# HC-SR04_v4_SCH.net
KiCad netlist of a schematic drawn in Altium Designer
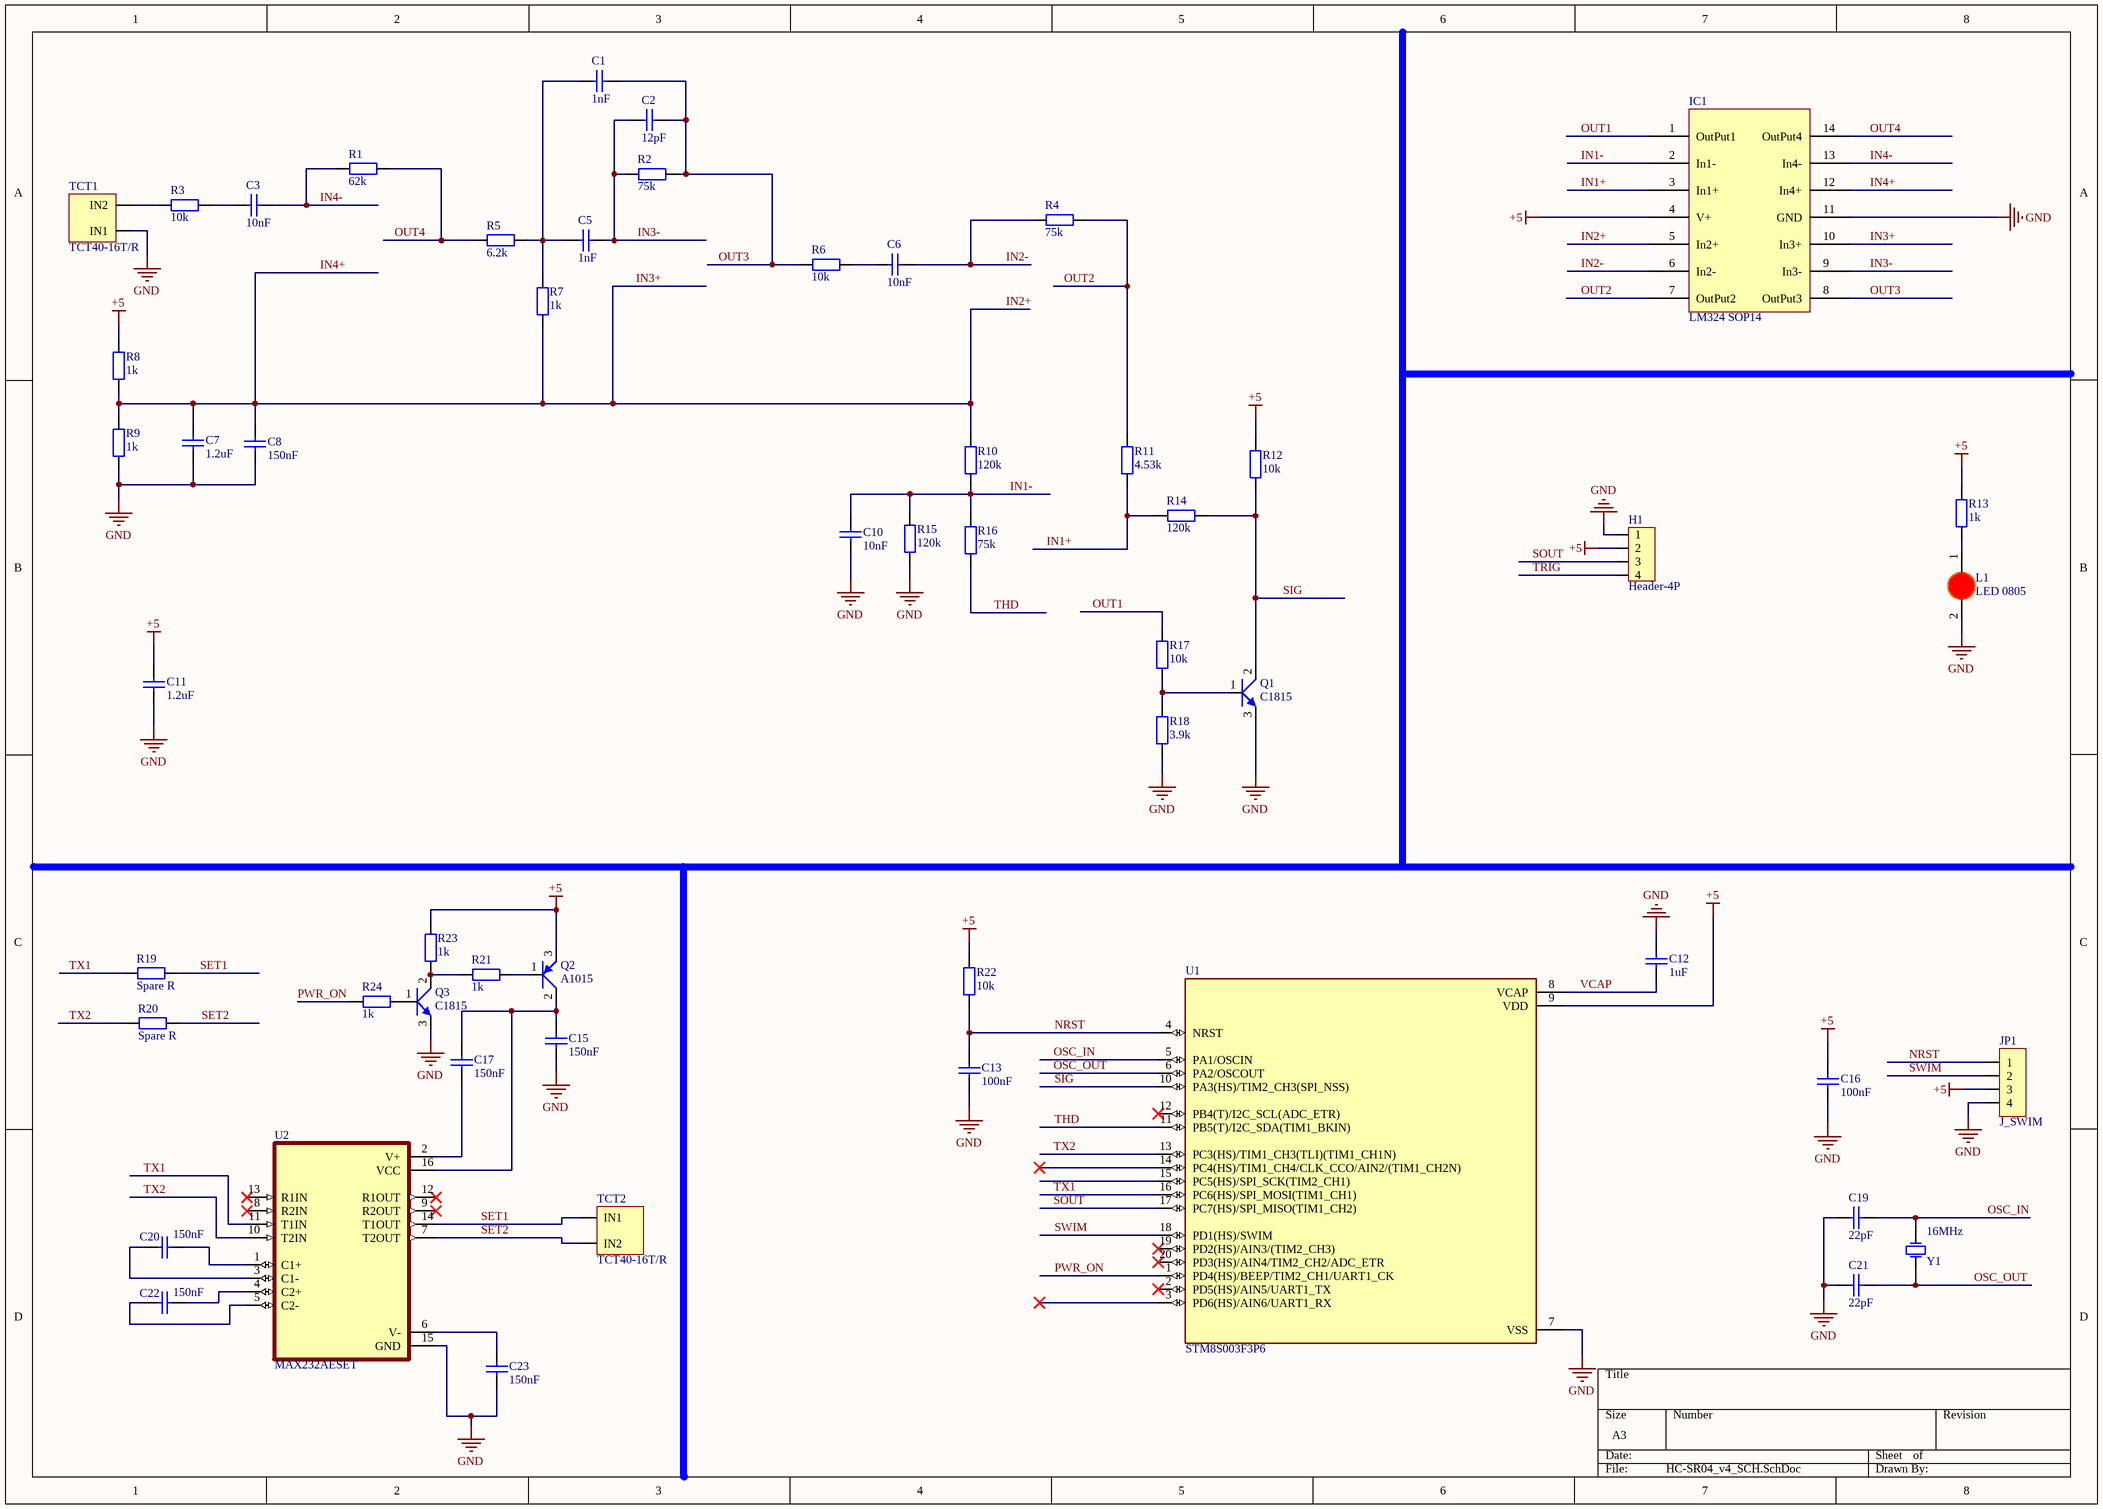
[diagram p0: HC-SR04_v4_SCH.SchDoc]

(export (version "E")
  (design (tool "Eeschema 10.0.6"))
  (components
    (comp (ref "C1")
      (value "1nF")
      (footprint "XLib:CAP_SMD_0603")
      (description "Dán")
      (libsource (lib "namnt_Lib") (part "Tu 0603 102 50V 10%"))
    )
    (comp (ref "C2")
      (value "12pF")
      (footprint "XLib:CAP_SMD_0603")
      (description "Dán")
      (libsource (lib "namnt_Lib") (part "Tu 0603 102 50V 10%"))
    )
    (comp (ref "C3")
      (value "10nF")
      (footprint "XLib:CAP_SMD_0603")
      (description "Dán")
      (libsource (lib "namnt_Lib") (part "Tu 0603 103 50V 10%"))
    )
    (comp (ref "C5")
      (value "1nF")
      (footprint "XLib:CAP_SMD_0603")
      (description "Dán")
      (libsource (lib "namnt_Lib") (part "Tu 0603 102 50V 10%"))
    )
    (comp (ref "C6")
      (value "10nF")
      (footprint "XLib:CAP_SMD_0603")
      (description "Dán")
      (libsource (lib "namnt_Lib") (part "Tu 0603 102 50V 10%"))
    )
    (comp (ref "C7")
      (value "1.2uF")
      (footprint "XLib:CAP_SMD_0603")
      (description "Dán")
      (libsource (lib "namnt_Lib") (part "Tu 0603 104 50V 10%"))
    )
    (comp (ref "C8")
      (value "150nF")
      (footprint "XLib:CAP_SMD_0603")
      (description "Dán")
      (libsource (lib "namnt_Lib") (part "Tu 0603 104 50V 10%"))
    )
    (comp (ref "C10")
      (value "10nF")
      (footprint "XLib:CAP_SMD_0603")
      (description "Dán")
      (libsource (lib "namnt_Lib") (part "Tu 0603 102 50V 10%"))
    )
    (comp (ref "C11")
      (value "1.2uF")
      (footprint "XLib:CAP_SMD_0603")
      (description "Dán")
      (libsource (lib "namnt_Lib") (part "Tu 0603 102 50V 10%"))
    )
    (comp (ref "C12")
      (value "1uF")
      (footprint "XLib:CAP_SMD_0603")
      (description "Dán")
      (libsource (lib "namnt_Lib") (part "Tu 0603 102 50V 10%"))
    )
    (comp (ref "C13")
      (value "100nF")
      (footprint "XLib:CAP_SMD_0603")
      (description "Dán")
      (libsource (lib "namnt_Lib") (part "Tu 0603 102 50V 10%"))
    )
    (comp (ref "C15")
      (value "150nF")
      (footprint "XLib:CAP_SMD_0603")
      (description "Dán")
      (libsource (lib "namnt_Lib") (part "Tu 0603 102 50V 10%"))
    )
    (comp (ref "C16")
      (value "100nF")
      (footprint "XLib:CAP_SMD_0603")
      (description "Dán")
      (libsource (lib "namnt_Lib") (part "Tu 0603 102 50V 10%"))
    )
    (comp (ref "C17")
      (value "150nF")
      (footprint "XLib:CAP_SMD_0603")
      (description "Dán")
      (libsource (lib "namnt_Lib") (part "Tu 0603 102 50V 10%"))
    )
    (comp (ref "C19")
      (value "22pF")
      (footprint "XLib:CAP_SMD_0603")
      (description "Dán")
      (libsource (lib "namnt_Lib") (part "Tu 0603 102 50V 10%"))
    )
    (comp (ref "C20")
      (value "150nF")
      (footprint "XLib:CAP_SMD_0603")
      (description "Dán")
      (libsource (lib "namnt_Lib") (part "Tu 0603 102 50V 10%"))
    )
    (comp (ref "C21")
      (value "22pF")
      (footprint "XLib:CAP_SMD_0603")
      (description "Dán")
      (libsource (lib "namnt_Lib") (part "Tu 0603 102 50V 10%"))
    )
    (comp (ref "C22")
      (value "150nF")
      (footprint "XLib:CAP_SMD_0603")
      (description "Dán")
      (libsource (lib "namnt_Lib") (part "Tu 0603 102 50V 10%"))
    )
    (comp (ref "C23")
      (value "150nF")
      (footprint "XLib:CAP_SMD_0603")
      (description "Dán")
      (libsource (lib "namnt_Lib") (part "Tu 0603 102 50V 10%"))
    )
    (comp (ref "H1")
      (value "Header-4P")
      (footprint "XLib:XH2.54_4P_MA")
      (description "Header")
      (fields
        (field (name "MANUFACTURER") "Würth Elektronik eiSos GmbH")
        (field (name "PARTNO") "613002143121")
        (field (name "CREATED BY") "Karrer Zheng")
      )
      (libsource (lib "XLib") (part "Header-4P"))
    )
    (comp (ref "IC1")
      (value "LM324 SOP14")
      (footprint "XLib:SOIC14")
      (description "Dán")
      (libsource (lib "namnt_Lib") (part "LM324 SOP14"))
    )
    (comp (ref "JP1")
      (value "J_SWIM")
      (footprint "JP 1x4 DT")
      (description "Cắm")
      (libsource (lib "namnt_Lib") (part "JP 1x4 2.54 Duc Thang"))
    )
    (comp (ref "L1")
      (value "LED 0805")
      (footprint "LED-0805-Red")
      (description "Dán")
      (libsource (lib "namnt_Lib") (part "LED 0805 Do"))
    )
    (comp (ref "Q1")
      (value "C1815")
      (footprint "XLib:SOT23")
      (libsource (lib "XLib") (part "Transistor_N_3P"))
    )
    (comp (ref "Q2")
      (value "A1015")
      (footprint "XLib:SOT23")
      (libsource (lib "XLib") (part "Transistor_P_3P"))
    )
    (comp (ref "Q3")
      (value "C1815")
      (footprint "XLib:SOT23")
      (libsource (lib "XLib") (part "Transistor_N_3P"))
    )
    (comp (ref "R1")
      (value "62k")
      (footprint "XLib:RES_SMD_0603")
      (description "Dán")
      (libsource (lib "namnt_Lib") (part "Tro 0603 1% 1k"))
    )
    (comp (ref "R2")
      (value "75k")
      (footprint "XLib:RES_SMD_0603")
      (description "Dán")
      (libsource (lib "namnt_Lib") (part "Tro 0603 1% 1k"))
    )
    (comp (ref "R3")
      (value "10k")
      (footprint "XLib:RES_SMD_0603")
      (description "Dán")
      (libsource (lib "namnt_Lib") (part "Tro 0603 1% 10k"))
    )
    (comp (ref "R4")
      (value "75k")
      (footprint "XLib:RES_SMD_0603")
      (description "Dán")
      (libsource (lib "namnt_Lib") (part "Tro 0603 1% 1k"))
    )
    (comp (ref "R5")
      (value "6.2k")
      (footprint "XLib:RES_SMD_0603")
      (description "Dán")
      (libsource (lib "namnt_Lib") (part "Tro 0603 1% 1k"))
    )
    (comp (ref "R6")
      (value "10k")
      (footprint "XLib:RES_SMD_0603")
      (description "Dán")
      (libsource (lib "namnt_Lib") (part "Tro 0603 1% 1k"))
    )
    (comp (ref "R7")
      (value "1k")
      (footprint "XLib:RES_SMD_0603")
      (description "Dán")
      (libsource (lib "namnt_Lib") (part "Tro 0603 1% 1k"))
    )
    (comp (ref "R8")
      (value "1k")
      (footprint "XLib:RES_SMD_0603")
      (description "Dán")
      (libsource (lib "namnt_Lib") (part "Tro 0603 1% 1k"))
    )
    (comp (ref "R9")
      (value "1k")
      (footprint "XLib:RES_SMD_0603")
      (description "Dán")
      (libsource (lib "namnt_Lib") (part "Tro 0603 1% 1k"))
    )
    (comp (ref "R10")
      (value "120k")
      (footprint "XLib:RES_SMD_0603")
      (description "Dán")
      (libsource (lib "namnt_Lib") (part "Tro 0603 1% 1k"))
    )
    (comp (ref "R11")
      (value "4.53k")
      (footprint "XLib:RES_SMD_0603")
      (description "Dán")
      (libsource (lib "namnt_Lib") (part "Tro 0603 1% 1k"))
    )
    (comp (ref "R12")
      (value "10k")
      (footprint "XLib:RES_SMD_0603")
      (description "Dán")
      (libsource (lib "namnt_Lib") (part "Tro 0603 1% 1k"))
    )
    (comp (ref "R13")
      (value "1k")
      (footprint "XLib:RES_SMD_0603")
      (description "Dán")
      (libsource (lib "namnt_Lib") (part "Tro 0603 1% 1k"))
    )
    (comp (ref "R14")
      (value "120k")
      (footprint "XLib:RES_SMD_0603")
      (description "Dán")
      (libsource (lib "namnt_Lib") (part "Tro 0603 1% 1k"))
    )
    (comp (ref "R15")
      (value "120k")
      (footprint "XLib:RES_SMD_0603")
      (description "Dán")
      (libsource (lib "namnt_Lib") (part "Tro 0603 1% 1k"))
    )
    (comp (ref "R16")
      (value "75k")
      (footprint "XLib:RES_SMD_0603")
      (description "Dán")
      (libsource (lib "namnt_Lib") (part "Tro 0603 1% 1k"))
    )
    (comp (ref "R17")
      (value "10k")
      (footprint "XLib:RES_SMD_0603")
      (description "Dán")
      (libsource (lib "namnt_Lib") (part "Tro 0603 1% 1k"))
    )
    (comp (ref "R18")
      (value "3.9k")
      (footprint "XLib:RES_SMD_0603")
      (description "Dán")
      (libsource (lib "namnt_Lib") (part "Tro 0603 1% 1k"))
    )
    (comp (ref "R19")
      (value "Spare R")
      (footprint "XLib:RES_SMD_0603")
      (description "Dán")
      (libsource (lib "namnt_Lib") (part "Tro 0603 1% 1k"))
    )
    (comp (ref "R20")
      (value "Spare R")
      (footprint "XLib:RES_SMD_0603")
      (description "Dán")
      (libsource (lib "namnt_Lib") (part "Tro 0603 1% 1k"))
    )
    (comp (ref "R21")
      (value "1k")
      (footprint "XLib:RES_SMD_0603")
      (description "Dán")
      (libsource (lib "namnt_Lib") (part "Tro 0603 1% 1k"))
    )
    (comp (ref "R22")
      (value "10k")
      (footprint "XLib:RES_SMD_0603")
      (description "Dán")
      (libsource (lib "namnt_Lib") (part "Tro 0603 1% 1k"))
    )
    (comp (ref "R23")
      (value "1k")
      (footprint "XLib:RES_SMD_0603")
      (description "Dán")
      (libsource (lib "namnt_Lib") (part "Tro 0603 1% 1k"))
    )
    (comp (ref "R24")
      (value "1k")
      (footprint "XLib:RES_SMD_0603")
      (description "Dán")
      (libsource (lib "namnt_Lib") (part "Tro 0603 1% 1k"))
    )
    (comp (ref "TCT1")
      (value "TCT40-16T/R")
      (footprint "TCT40")
      (description "Piezoelectric Ceramic Ultrasonic Sensor")
      (libsource (lib "") (part "TCT40-16T/R_1"))
    )
    (comp (ref "TCT2")
      (value "TCT40-16T/R")
      (footprint "TCT40")
      (description "Piezoelectric Ceramic Ultrasonic Sensor")
      (libsource (lib "namnt_Lib") (part "TCT40-16T/R"))
    )
    (comp (ref "U1")
      (value "STM8S003F3P6")
      (footprint "SOP65P640X120-20N")
      (description "STM8 series Microcontroller IC 8-Bit 16MHz 8KB (8K x 8) FLASH 20-TSSOP")
      (fields (field (name "MF") "STMicroelectronics"))
      (libsource (lib "namnt_Lib") (part "STM8S003F3P6"))
    )
    (comp (ref "U2")
      (value "MAX232AESET")
      (footprint "XLib:SOIC16")
      (description "Dual Transmitter/Receiver RS-232 16-Pin SOIC N Tube")
      (fields (field (name "MF") "Analog Devices") (field (name "MP") "MAX232AESE+"))
      (libsource (lib "namnt_Lib") (part "MAX232AESET"))
    )
    (comp (ref "Y1")
      (value "16MHz")
      (footprint "THACH ANH DAN 3215")
      (description "C700805")
      (libsource (lib "namnt_Lib") (part "Thach Anh SMD 3225"))
    )
  )
  (nets
    (net (code "1") (name "+5") (class "Default")
      (node (ref "C11") (pin "1") (pinfunction "1_1") (pintype "passive"))
      (node (ref "C16") (pin "1") (pinfunction "1_1") (pintype "passive"))
      (node (ref "H1") (pin "2") (pinfunction "2_2") (pintype "passive"))
      (node (ref "IC1") (pin "4") (pinfunction "V+_4") (pintype "passive"))
      (node (ref "JP1") (pin "3") (pinfunction "3_3") (pintype "passive"))
      (node (ref "Q2") (pin "3") (pinfunction "E_3") (pintype "passive"))
      (node (ref "R12") (pin "2") (pinfunction "2_2") (pintype "passive"))
      (node (ref "R13") (pin "2") (pinfunction "2_2") (pintype "passive"))
      (node (ref "R22") (pin "1") (pinfunction "1_1") (pintype "passive"))
      (node (ref "R23") (pin "1") (pinfunction "1_1") (pintype "passive"))
      (node (ref "R8") (pin "2") (pinfunction "2_2") (pintype "passive"))
      (node (ref "U1") (pin "9") (pinfunction "VDD_9") (pintype "power_in"))
    )
    (net (code "2") (name "/IN1+") (class "Default")
      (node (ref "IC1") (pin "3") (pinfunction "In1+_3") (pintype "passive"))
      (node (ref "R11") (pin "2") (pinfunction "2_2") (pintype "passive"))
      (node (ref "R14") (pin "1") (pinfunction "1_1") (pintype "passive"))
    )
    (net (code "3") (name "/IN1-") (class "Default")
      (node (ref "C10") (pin "1") (pinfunction "1_1") (pintype "passive"))
      (node (ref "IC1") (pin "2") (pinfunction "In1-_2") (pintype "passive"))
      (node (ref "R10") (pin "2") (pinfunction "2_2") (pintype "passive"))
      (node (ref "R15") (pin "2") (pinfunction "2_2") (pintype "passive"))
      (node (ref "R16") (pin "2") (pinfunction "2_2") (pintype "passive"))
    )
    (net (code "4") (name "/IN2+") (class "Default")
      (node (ref "C7") (pin "1") (pinfunction "1_1") (pintype "passive"))
      (node (ref "C8") (pin "1") (pinfunction "1_1") (pintype "passive"))
      (node (ref "IC1") (pin "10") (pinfunction "In3+_10") (pintype "passive"))
      (node (ref "IC1") (pin "12") (pinfunction "In4+_12") (pintype "passive"))
      (node (ref "IC1") (pin "5") (pinfunction "In2+_5") (pintype "passive"))
      (node (ref "R10") (pin "1") (pinfunction "1_1") (pintype "passive"))
      (node (ref "R7") (pin "2") (pinfunction "2_2") (pintype "passive"))
      (node (ref "R8") (pin "1") (pinfunction "1_1") (pintype "passive"))
      (node (ref "R9") (pin "2") (pinfunction "2_2") (pintype "passive"))
    )
    (net (code "5") (name "/IN2-") (class "Default")
      (node (ref "C6") (pin "1") (pinfunction "1_1") (pintype "passive"))
      (node (ref "IC1") (pin "6") (pinfunction "In2-_6") (pintype "passive"))
      (node (ref "R4") (pin "2") (pinfunction "2_2") (pintype "passive"))
    )
    (net (code "6") (name "/IN3-") (class "Default")
      (node (ref "C2") (pin "2") (pinfunction "2_2") (pintype "passive"))
      (node (ref "C5") (pin "1") (pinfunction "1_1") (pintype "passive"))
      (node (ref "IC1") (pin "9") (pinfunction "In3-_9") (pintype "passive"))
      (node (ref "R2") (pin "2") (pinfunction "2_2") (pintype "passive"))
    )
    (net (code "7") (name "/IN4-") (class "Default")
      (node (ref "C3") (pin "2") (pinfunction "2_2") (pintype "passive"))
      (node (ref "IC1") (pin "13") (pinfunction "In4-_13") (pintype "passive"))
      (node (ref "R1") (pin "2") (pinfunction "2_2") (pintype "passive"))
    )
    (net (code "8") (name "/NRST") (class "Default")
      (node (ref "C13") (pin "1") (pinfunction "1_1") (pintype "passive"))
      (node (ref "JP1") (pin "1") (pinfunction "1_1") (pintype "passive"))
      (node (ref "R22") (pin "2") (pinfunction "2_2") (pintype "passive"))
      (node (ref "U1") (pin "4") (pinfunction "NRST_4") (pintype "bidirectional"))
    )
    (net (code "9") (name "/OSC_IN") (class "Default")
      (node (ref "C19") (pin "2") (pinfunction "2_2") (pintype "passive"))
      (node (ref "U1") (pin "5") (pinfunction "PA1/OSCIN_5") (pintype "bidirectional"))
      (node (ref "Y1") (pin "2") (pinfunction "OSC2_2") (pintype "passive"))
    )
    (net (code "10") (name "/OSC_OUT") (class "Default")
      (node (ref "C21") (pin "2") (pinfunction "2_2") (pintype "passive"))
      (node (ref "U1") (pin "6") (pinfunction "PA2/OSCOUT_6") (pintype "bidirectional"))
      (node (ref "Y1") (pin "1") (pinfunction "OSC1_1") (pintype "passive"))
    )
    (net (code "11") (name "/OUT1") (class "Default")
      (node (ref "IC1") (pin "1") (pinfunction "OutPut1_1") (pintype "passive"))
      (node (ref "R17") (pin "2") (pinfunction "2_2") (pintype "passive"))
    )
    (net (code "12") (name "/OUT2") (class "Default")
      (node (ref "IC1") (pin "7") (pinfunction "OutPut2_7") (pintype "passive"))
      (node (ref "R11") (pin "1") (pinfunction "1_1") (pintype "passive"))
      (node (ref "R4") (pin "1") (pinfunction "1_1") (pintype "passive"))
    )
    (net (code "13") (name "/OUT3") (class "Default")
      (node (ref "C1") (pin "1") (pinfunction "1_1") (pintype "passive"))
      (node (ref "C2") (pin "1") (pinfunction "1_1") (pintype "passive"))
      (node (ref "IC1") (pin "8") (pinfunction "OutPut3_8") (pintype "passive"))
      (node (ref "R2") (pin "1") (pinfunction "1_1") (pintype "passive"))
      (node (ref "R6") (pin "2") (pinfunction "2_2") (pintype "passive"))
    )
    (net (code "14") (name "/OUT4") (class "Default")
      (node (ref "IC1") (pin "14") (pinfunction "OutPut4_14") (pintype "passive"))
      (node (ref "R1") (pin "1") (pinfunction "1_1") (pintype "passive"))
      (node (ref "R5") (pin "2") (pinfunction "2_2") (pintype "passive"))
    )
    (net (code "15") (name "/PWR_ON") (class "Default")
      (node (ref "R24") (pin "2") (pinfunction "2_2") (pintype "passive"))
      (node (ref "U1") (pin "1") (pinfunction "PD4(HS)/BEEP/TIM2_CH1/UART1_CK_1") (pintype "bidirectional"))
    )
    (net (code "16") (name "/SET1") (class "Default")
      (node (ref "R19") (pin "2") (pinfunction "2_2") (pintype "passive"))
      (node (ref "TCT2") (pin "1") (pinfunction "IN1_1") (pintype "passive"))
      (node (ref "U2") (pin "14") (pinfunction "T1OUT_14") (pintype "output"))
    )
    (net (code "17") (name "/SET2") (class "Default")
      (node (ref "R20") (pin "2") (pinfunction "2_2") (pintype "passive"))
      (node (ref "TCT2") (pin "2") (pinfunction "IN2_2") (pintype "passive"))
      (node (ref "U2") (pin "7") (pinfunction "T2OUT_7") (pintype "output"))
    )
    (net (code "18") (name "/SIG") (class "Default")
      (node (ref "Q1") (pin "2") (pinfunction "C_2") (pintype "passive"))
      (node (ref "R12") (pin "1") (pinfunction "1_1") (pintype "passive"))
      (node (ref "R14") (pin "2") (pinfunction "2_2") (pintype "passive"))
      (node (ref "U1") (pin "10") (pinfunction "PA3(HS)/TIM2_CH3(SPI_NSS)_10") (pintype "bidirectional"))
    )
    (net (code "19") (name "/SOUT") (class "Default")
      (node (ref "H1") (pin "3") (pinfunction "3_3") (pintype "passive"))
      (node (ref "U1") (pin "17") (pinfunction "PC7(HS)/SPI_MISO(TIM1_CH2)_17") (pintype "bidirectional"))
    )
    (net (code "20") (name "/SWIM") (class "Default")
      (node (ref "JP1") (pin "2") (pinfunction "2_2") (pintype "passive"))
      (node (ref "U1") (pin "18") (pinfunction "PD1(HS)/SWIM_18") (pintype "bidirectional"))
    )
    (net (code "21") (name "/THD") (class "Default")
      (node (ref "R16") (pin "1") (pinfunction "1_1") (pintype "passive"))
      (node (ref "U1") (pin "11") (pinfunction "PB5(T)/I2C_SDA(TIM1_BKIN)_11") (pintype "bidirectional"))
    )
    (net (code "22") (name "/TRIG") (class "Default")
      (node (ref "H1") (pin "4") (pinfunction "4_4") (pintype "passive"))
    )
    (net (code "23") (name "/TX1") (class "Default")
      (node (ref "R19") (pin "1") (pinfunction "1_1") (pintype "passive"))
      (node (ref "U1") (pin "16") (pinfunction "PC6(HS)/SPI_MOSI(TIM1_CH1)_16") (pintype "bidirectional"))
      (node (ref "U2") (pin "11") (pinfunction "T1IN_11") (pintype "input"))
    )
    (net (code "24") (name "/TX2") (class "Default")
      (node (ref "R20") (pin "1") (pinfunction "1_1") (pintype "passive"))
      (node (ref "U1") (pin "13") (pinfunction "PC3(HS)/TIM1_CH3(TLI)(TIM1_CH1N)_13") (pintype "bidirectional"))
      (node (ref "U2") (pin "10") (pinfunction "T2IN_10") (pintype "input"))
    )
    (net (code "25") (name "/VCAP") (class "Default")
      (node (ref "C12") (pin "2") (pinfunction "2_2") (pintype "passive"))
      (node (ref "U1") (pin "8") (pinfunction "VCAP_8") (pintype "power_in"))
    )
    (net (code "26") (name "GND") (class "Default")
      (node (ref "C10") (pin "2") (pinfunction "2_2") (pintype "passive"))
      (node (ref "C11") (pin "2") (pinfunction "2_2") (pintype "passive"))
      (node (ref "C12") (pin "1") (pinfunction "1_1") (pintype "passive"))
      (node (ref "C13") (pin "2") (pinfunction "2_2") (pintype "passive"))
      (node (ref "C15") (pin "2") (pinfunction "2_2") (pintype "passive"))
      (node (ref "C16") (pin "2") (pinfunction "2_2") (pintype "passive"))
      (node (ref "C19") (pin "1") (pinfunction "1_1") (pintype "passive"))
      (node (ref "C21") (pin "1") (pinfunction "1_1") (pintype "passive"))
      (node (ref "C23") (pin "2") (pinfunction "2_2") (pintype "passive"))
      (node (ref "C7") (pin "2") (pinfunction "2_2") (pintype "passive"))
      (node (ref "C8") (pin "2") (pinfunction "2_2") (pintype "passive"))
      (node (ref "H1") (pin "1") (pinfunction "1_1") (pintype "passive"))
      (node (ref "IC1") (pin "11") (pinfunction "GND_11") (pintype "passive"))
      (node (ref "JP1") (pin "4") (pinfunction "4_4") (pintype "passive"))
      (node (ref "L1") (pin "2") (pinfunction "K_2") (pintype "passive"))
      (node (ref "Q1") (pin "3") (pinfunction "E_3") (pintype "passive"))
      (node (ref "Q3") (pin "3") (pinfunction "E_3") (pintype "passive"))
      (node (ref "R15") (pin "1") (pinfunction "1_1") (pintype "passive"))
      (node (ref "R18") (pin "1") (pinfunction "1_1") (pintype "passive"))
      (node (ref "R9") (pin "1") (pinfunction "1_1") (pintype "passive"))
      (node (ref "TCT1") (pin "1") (pinfunction "IN1_1") (pintype "passive"))
      (node (ref "U1") (pin "7") (pinfunction "VSS_7") (pintype "power_in"))
      (node (ref "U2") (pin "15") (pinfunction "GND_15") (pintype "power_in"))
    )
    (net (code "27") (name "Net-(C1-Pad2)") (class "Default")
      (node (ref "C1") (pin "2") (pinfunction "2_2") (pintype "passive"))
      (node (ref "C5") (pin "2") (pinfunction "2_2") (pintype "passive"))
      (node (ref "R5") (pin "1") (pinfunction "1_1") (pintype "passive"))
      (node (ref "R7") (pin "1") (pinfunction "1_1") (pintype "passive"))
    )
    (net (code "28") (name "Net-(C3-Pad1)") (class "Default")
      (node (ref "C3") (pin "1") (pinfunction "1_1") (pintype "passive"))
      (node (ref "R3") (pin "2") (pinfunction "2_2") (pintype "passive"))
    )
    (net (code "29") (name "Net-(C6-Pad2)") (class "Default")
      (node (ref "C6") (pin "2") (pinfunction "2_2") (pintype "passive"))
      (node (ref "R6") (pin "1") (pinfunction "1_1") (pintype "passive"))
    )
    (net (code "30") (name "Net-(L1-A)") (class "Default")
      (node (ref "L1") (pin "1") (pinfunction "A_1") (pintype "passive"))
      (node (ref "R13") (pin "1") (pinfunction "1_1") (pintype "passive"))
    )
    (net (code "31") (name "Net-(Q1-B)") (class "Default")
      (node (ref "Q1") (pin "1") (pinfunction "B_1") (pintype "passive"))
      (node (ref "R17") (pin "1") (pinfunction "1_1") (pintype "passive"))
      (node (ref "R18") (pin "2") (pinfunction "2_2") (pintype "passive"))
    )
    (net (code "32") (name "Net-(Q2-B)") (class "Default")
      (node (ref "Q2") (pin "1") (pinfunction "B_1") (pintype "passive"))
      (node (ref "R21") (pin "1") (pinfunction "1_1") (pintype "passive"))
    )
    (net (code "33") (name "Net-(Q2-C)") (class "Default")
      (node (ref "C15") (pin "1") (pinfunction "1_1") (pintype "passive"))
      (node (ref "C17") (pin "1") (pinfunction "1_1") (pintype "passive"))
      (node (ref "Q2") (pin "2") (pinfunction "C_2") (pintype "passive"))
      (node (ref "U2") (pin "16") (pinfunction "VCC_16") (pintype "power_in"))
    )
    (net (code "34") (name "Net-(Q3-B)") (class "Default")
      (node (ref "Q3") (pin "1") (pinfunction "B_1") (pintype "passive"))
      (node (ref "R24") (pin "1") (pinfunction "1_1") (pintype "passive"))
    )
    (net (code "35") (name "Net-(Q3-C)") (class "Default")
      (node (ref "Q3") (pin "2") (pinfunction "C_2") (pintype "passive"))
      (node (ref "R21") (pin "2") (pinfunction "2_2") (pintype "passive"))
      (node (ref "R23") (pin "2") (pinfunction "2_2") (pintype "passive"))
    )
    (net (code "36") (name "Net-(TCT1-IN2)") (class "Default")
      (node (ref "R3") (pin "1") (pinfunction "1_1") (pintype "passive"))
      (node (ref "TCT1") (pin "2") (pinfunction "IN2_2") (pintype "passive"))
    )
    (net (code "37") (name "Net-(U2-C1+)") (class "Default")
      (node (ref "C20") (pin "2") (pinfunction "2_2") (pintype "passive"))
      (node (ref "U2") (pin "1") (pinfunction "C1+_1") (pintype "bidirectional"))
    )
    (net (code "38") (name "Net-(U2-C1-)") (class "Default")
      (node (ref "C20") (pin "1") (pinfunction "1_1") (pintype "passive"))
      (node (ref "U2") (pin "3") (pinfunction "C1-_3") (pintype "bidirectional"))
    )
    (net (code "39") (name "Net-(U2-C2+)") (class "Default")
      (node (ref "C22") (pin "2") (pinfunction "2_2") (pintype "passive"))
      (node (ref "U2") (pin "4") (pinfunction "C2+_4") (pintype "bidirectional"))
    )
    (net (code "40") (name "Net-(U2-C2-)") (class "Default")
      (node (ref "C22") (pin "1") (pinfunction "1_1") (pintype "passive"))
      (node (ref "U2") (pin "5") (pinfunction "C2-_5") (pintype "bidirectional"))
    )
    (net (code "41") (name "Net-(U2-V+)") (class "Default")
      (node (ref "C17") (pin "2") (pinfunction "2_2") (pintype "passive"))
      (node (ref "U2") (pin "2") (pinfunction "V+_2") (pintype "power_in"))
    )
    (net (code "42") (name "Net-(U2-V-)") (class "Default")
      (node (ref "C23") (pin "1") (pinfunction "1_1") (pintype "passive"))
      (node (ref "U2") (pin "6") (pinfunction "V-_6") (pintype "power_in"))
    )
    (net (code "43") (name "unconnected-(U1-PB4(T){slash}I2C_SCL(ADC_ETR)-Pad12)") (class "Default")
      (node (ref "U1") (pin "12") (pinfunction "PB4(T)/I2C_SCL(ADC_ETR)_12") (pintype "bidirectional+no_connect"))
    )
    (net (code "44") (name "unconnected-(U1-PC4(HS){slash}TIM1_CH4{slash}CLK_CCO{slash}AIN2{slash}(TIM1_CH2N)-Pad14)") (class "Default")
      (node (ref "U1") (pin "14") (pinfunction "PC4(HS)/TIM1_CH4/CLK_CCO/AIN2/(TIM1_CH2N)_14") (pintype "bidirectional+no_connect"))
    )
    (net (code "45") (name "unconnected-(U1-PC5(HS){slash}SPI_SCK(TIM2_CH1)-Pad15)") (class "Default")
      (node (ref "U1") (pin "15") (pinfunction "PC5(HS)/SPI_SCK(TIM2_CH1)_15") (pintype "bidirectional"))
    )
    (net (code "46") (name "unconnected-(U1-PD2(HS){slash}AIN3{slash}(TIM2_CH3)-Pad19)") (class "Default")
      (node (ref "U1") (pin "19") (pinfunction "PD2(HS)/AIN3/(TIM2_CH3)_19") (pintype "bidirectional+no_connect"))
    )
    (net (code "47") (name "unconnected-(U1-PD3(HS){slash}AIN4{slash}TIM2_CH2{slash}ADC_ETR-Pad20)") (class "Default")
      (node (ref "U1") (pin "20") (pinfunction "PD3(HS)/AIN4/TIM2_CH2/ADC_ETR_20") (pintype "bidirectional+no_connect"))
    )
    (net (code "48") (name "unconnected-(U1-PD5(HS){slash}AIN5{slash}UART1_TX-Pad2)") (class "Default")
      (node (ref "U1") (pin "2") (pinfunction "PD5(HS)/AIN5/UART1_TX_2") (pintype "bidirectional+no_connect"))
    )
    (net (code "49") (name "unconnected-(U1-PD6(HS){slash}AIN6{slash}UART1_RX-Pad3)") (class "Default")
      (node (ref "U1") (pin "3") (pinfunction "PD6(HS)/AIN6/UART1_RX_3") (pintype "bidirectional+no_connect"))
    )
    (net (code "50") (name "unconnected-(U2-R1IN-Pad13)") (class "Default")
      (node (ref "U2") (pin "13") (pinfunction "R1IN_13") (pintype "input+no_connect"))
    )
    (net (code "51") (name "unconnected-(U2-R1OUT-Pad12)") (class "Default")
      (node (ref "U2") (pin "12") (pinfunction "R1OUT_12") (pintype "output+no_connect"))
    )
    (net (code "52") (name "unconnected-(U2-R2IN-Pad8)") (class "Default")
      (node (ref "U2") (pin "8") (pinfunction "R2IN_8") (pintype "input+no_connect"))
    )
    (net (code "53") (name "unconnected-(U2-R2OUT-Pad9)") (class "Default")
      (node (ref "U2") (pin "9") (pinfunction "R2OUT_9") (pintype "output+no_connect"))
    )
  )
)
